# slow-movie-player.net
KiCad netlist of a schematic drawn in EasyEDA Pro
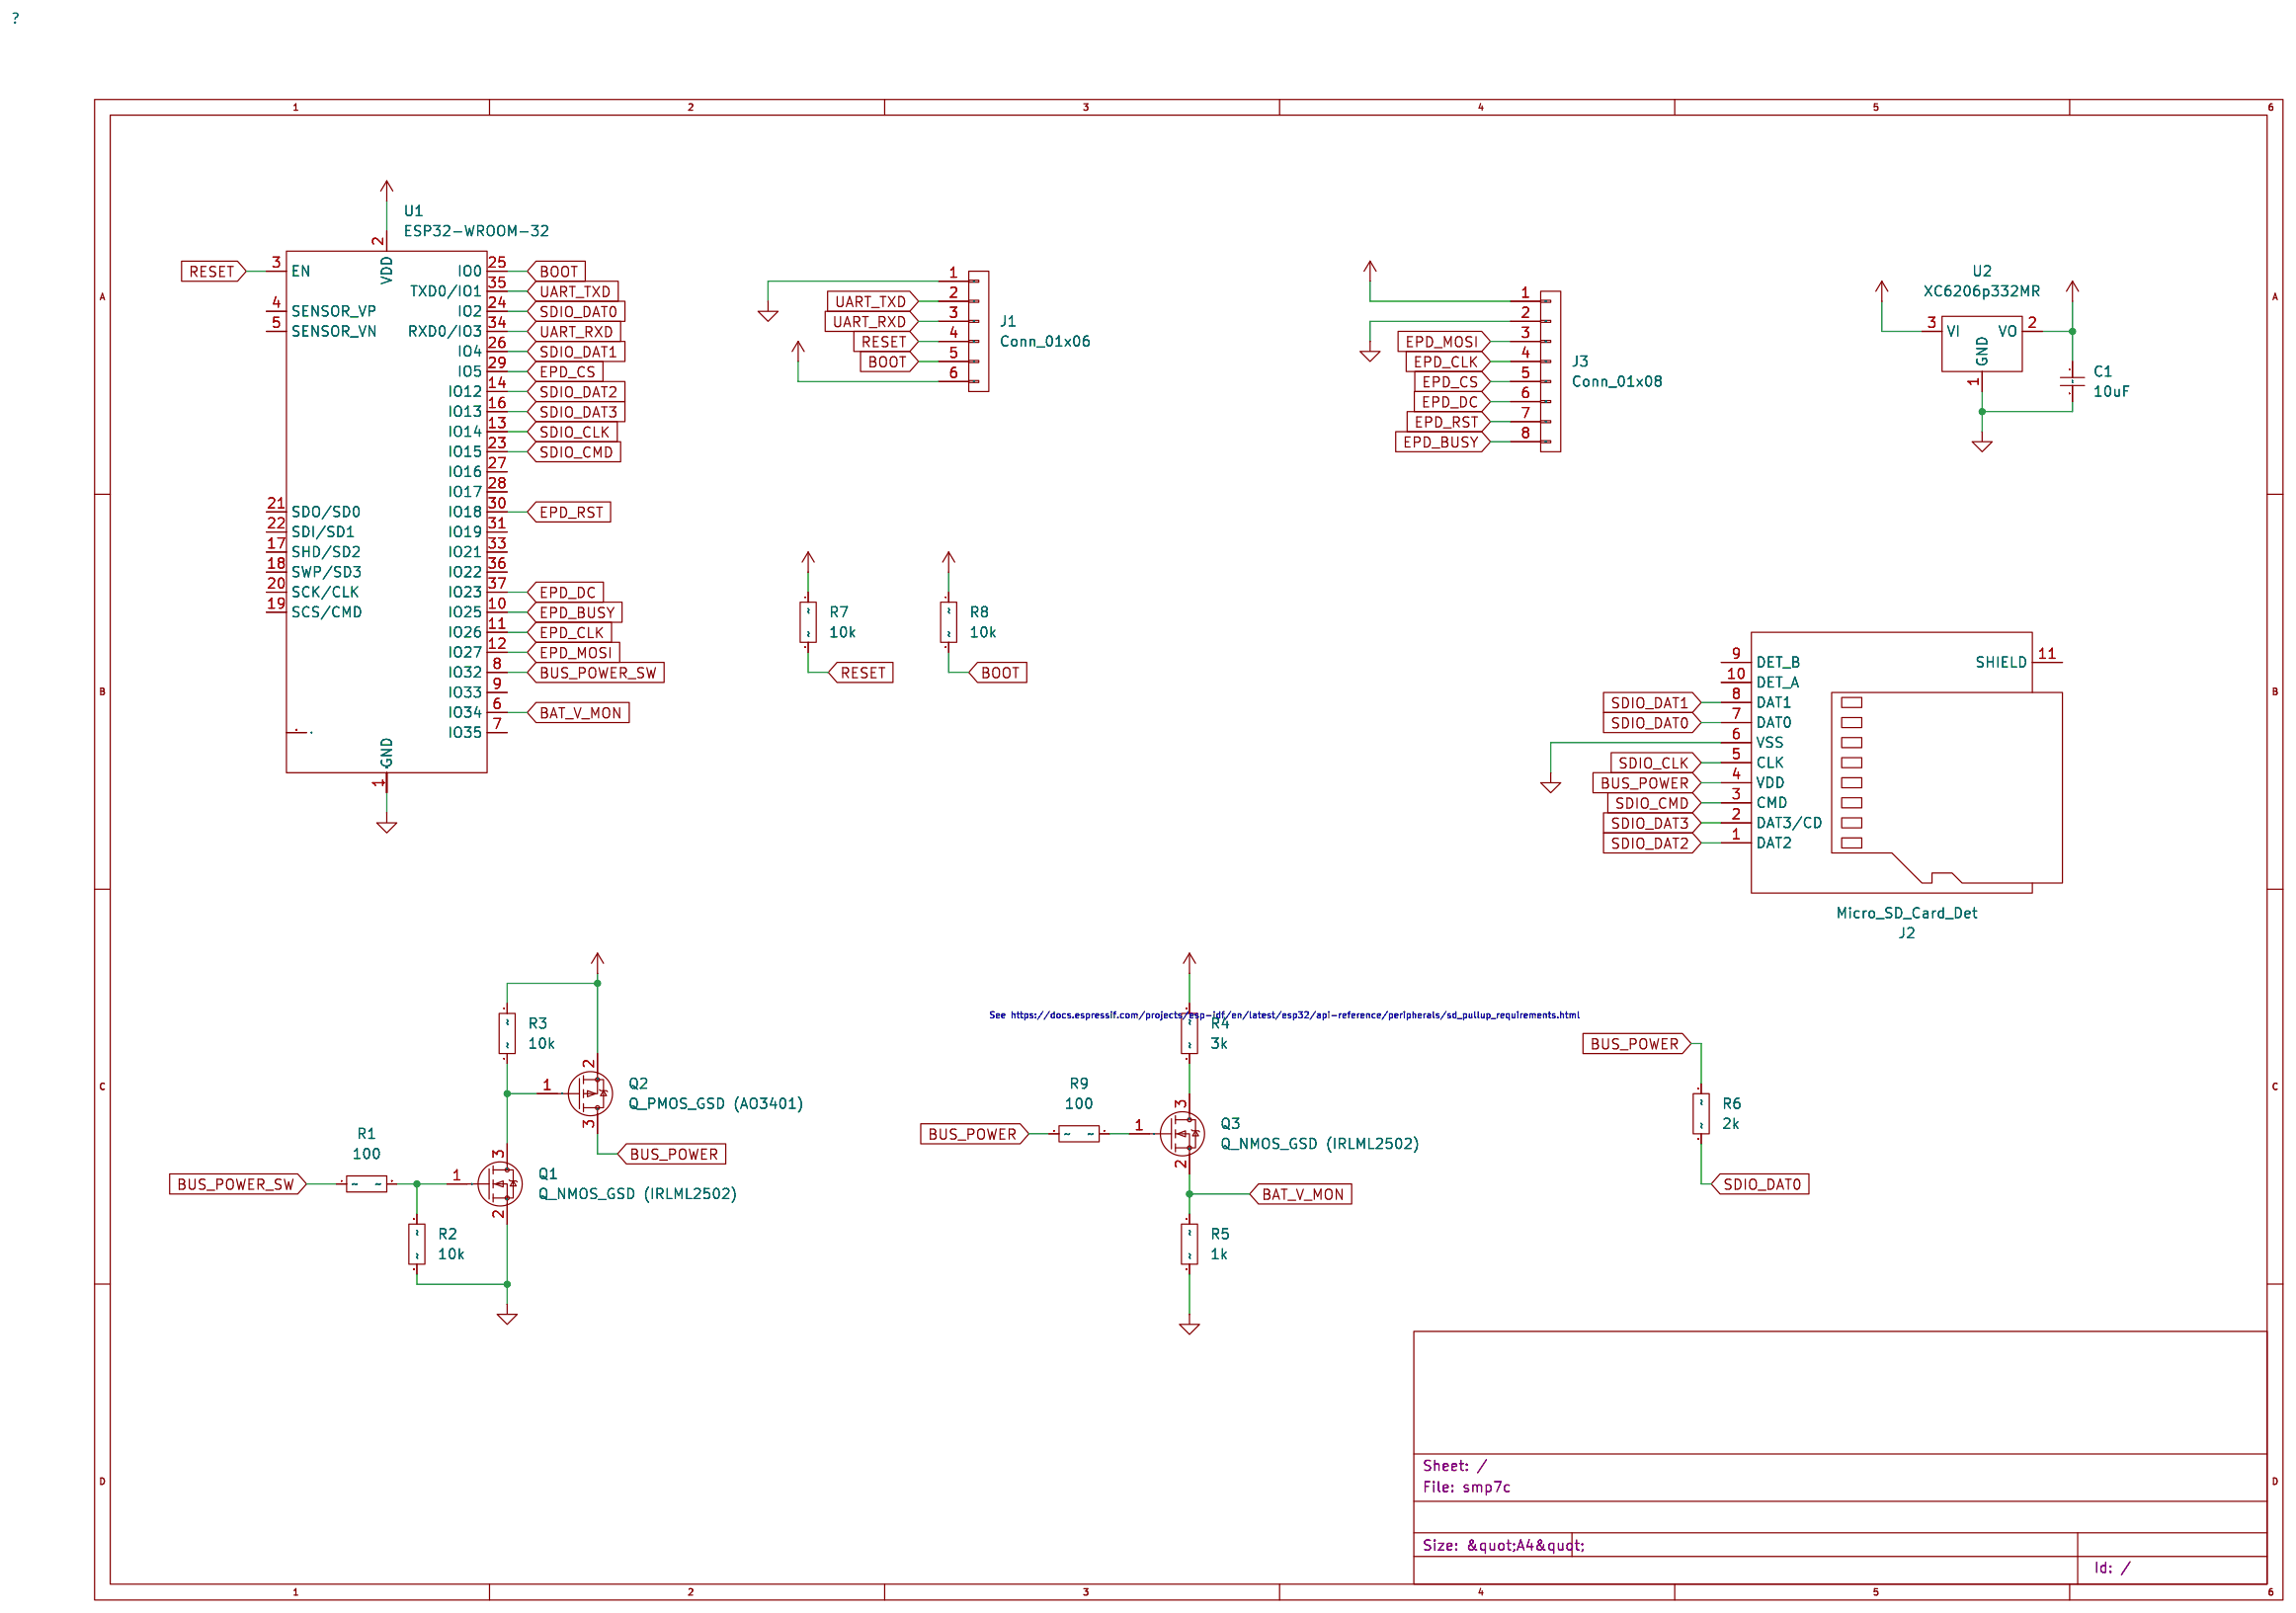
[diagram p0: schematic sheet]

(export (version "E")
  (design (tool "Eeschema 10.0.6"))
  (components
    (comp (ref "C1")
      (value "10uF")
      (footprint "easyedapro:Capacitor_SMD:C_1206_3216Metric")
      (libsource (lib "easyedapro") (part "Device_C_Small"))
    )
    (comp (ref "J1")
      (value "Conn_01x06")
      (footprint "easyedapro:Connector_PinSocket_2.54mm:PinSocket_1x06_P2.54mm_Vertical")
      (libsource (lib "easyedapro") (part "Connector_Generic_Conn_01x06"))
    )
    (comp (ref "J2")
      (value "Micro_SD_Card_Det")
      (footprint "easyedapro:Connector_Card:microSD_HC_Hirose_DM3BT-DSF-PEJS")
      (libsource (lib "easyedapro") (part "Connector_Micro_SD_Card_Det"))
    )
    (comp (ref "J3")
      (value "Conn_01x08")
      (footprint "easyedapro:Connector_PinSocket_2.54mm:PinSocket_1x08_P2.54mm_Vertical")
      (libsource (lib "easyedapro") (part "Connector_Generic_Conn_01x08"))
    )
    (comp (ref "Q1")
      (value "Q_NMOS_GSD (IRLML2502)")
      (footprint "easyedapro:Package_TO_SOT_SMD:SOT-23")
      (libsource (lib "easyedapro") (part "Device_Q_NMOS_GSD"))
    )
    (comp (ref "Q2")
      (value "Q_PMOS_GSD (AO3401)")
      (footprint "easyedapro:Package_TO_SOT_SMD:SOT-23")
      (libsource (lib "easyedapro") (part "Device_Q_PMOS_GSD"))
    )
    (comp (ref "Q3")
      (value "Q_NMOS_GSD (IRLML2502)")
      (footprint "easyedapro:Package_TO_SOT_SMD:SOT-23")
      (libsource (lib "easyedapro") (part "Device_Q_NMOS_GSD"))
    )
    (comp (ref "R1")
      (value "100")
      (footprint "easyedapro:Resistor_SMD:R_0603_1608Metric")
      (libsource (lib "easyedapro") (part "Device_R"))
    )
    (comp (ref "R2")
      (value "10k")
      (footprint "easyedapro:Resistor_SMD:R_0603_1608Metric")
      (libsource (lib "easyedapro") (part "Device_R"))
    )
    (comp (ref "R3")
      (value "10k")
      (footprint "easyedapro:Resistor_SMD:R_0603_1608Metric")
      (libsource (lib "easyedapro") (part "Device_R"))
    )
    (comp (ref "R4")
      (value "3k")
      (footprint "easyedapro:Resistor_SMD:R_0603_1608Metric")
      (libsource (lib "easyedapro") (part "Device_R"))
    )
    (comp (ref "R5")
      (value "1k")
      (footprint "easyedapro:Resistor_SMD:R_0603_1608Metric")
      (libsource (lib "easyedapro") (part "Device_R"))
    )
    (comp (ref "R6")
      (value "2k")
      (footprint "easyedapro:Resistor_SMD:R_0603_1608Metric")
      (libsource (lib "easyedapro") (part "Device_R"))
    )
    (comp (ref "R7")
      (value "10k")
      (footprint "easyedapro:Resistor_SMD:R_0603_1608Metric")
      (libsource (lib "easyedapro") (part "Device_R"))
    )
    (comp (ref "R8")
      (value "10k")
      (footprint "easyedapro:Resistor_SMD:R_0603_1608Metric")
      (libsource (lib "easyedapro") (part "Device_R"))
    )
    (comp (ref "R9")
      (value "100")
      (footprint "easyedapro:Resistor_SMD:R_0603_1608Metric")
      (libsource (lib "easyedapro") (part "Device_R"))
    )
    (comp (ref "U1")
      (value "ESP32-WROOM-32")
      (footprint "easyedapro:RF_Module:ESP32-WROOM-32")
      (libsource (lib "easyedapro") (part "RF_Module_ESP32-WROOM-32"))
    )
    (comp (ref "U2")
      (value "XC6206p332MR")
      (footprint "easyedapro:Package_TO_SOT_SMD:SOT-23")
      (libsource (lib "easyedapro") (part "Regulator_Linear_XC6206PxxxMR"))
    )
  )
  (nets
    (net (code "1") (name "BAT_V_MON") (class "Default")
      (node (ref "Q3") (pin "2") (pinfunction "S_2") (pintype "unspecified"))
      (node (ref "R5") (pin "1") (pinfunction "~_1") (pintype "unspecified"))
      (node (ref "U1") (pin "6") (pinfunction "IO34_6") (pintype "input"))
    )
    (net (code "2") (name "BOOT") (class "Default")
      (node (ref "J1") (pin "5") (pinfunction "Pin_5_5") (pintype "unspecified"))
      (node (ref "R8") (pin "2") (pinfunction "~_2") (pintype "unspecified"))
      (node (ref "U1") (pin "25") (pinfunction "IO0_25") (pintype "bidirectional"))
    )
    (net (code "3") (name "BUS_POWER") (class "Default")
      (node (ref "J2") (pin "4") (pinfunction "VDD_4") (pintype "unspecified"))
      (node (ref "Q2") (pin "3") (pinfunction "D_3") (pintype "unspecified"))
      (node (ref "R6") (pin "1") (pinfunction "~_1") (pintype "unspecified"))
      (node (ref "R9") (pin "1") (pinfunction "~_1") (pintype "unspecified"))
    )
    (net (code "4") (name "BUS_POWER_SW") (class "Default")
      (node (ref "R1") (pin "1") (pinfunction "~_1") (pintype "unspecified"))
      (node (ref "U1") (pin "8") (pinfunction "IO32_8") (pintype "bidirectional"))
    )
    (net (code "5") (name "EPD_BUSY") (class "Default")
      (node (ref "J3") (pin "8") (pinfunction "Pin_8_8") (pintype "unspecified"))
      (node (ref "U1") (pin "10") (pinfunction "IO25_10") (pintype "bidirectional"))
    )
    (net (code "6") (name "EPD_CLK") (class "Default")
      (node (ref "J3") (pin "4") (pinfunction "Pin_4_4") (pintype "unspecified"))
      (node (ref "U1") (pin "11") (pinfunction "IO26_11") (pintype "bidirectional"))
    )
    (net (code "7") (name "EPD_CS") (class "Default")
      (node (ref "J3") (pin "5") (pinfunction "Pin_5_5") (pintype "unspecified"))
      (node (ref "U1") (pin "29") (pinfunction "IO5_29") (pintype "bidirectional"))
    )
    (net (code "8") (name "EPD_DC") (class "Default")
      (node (ref "J3") (pin "6") (pinfunction "Pin_6_6") (pintype "unspecified"))
      (node (ref "U1") (pin "37") (pinfunction "IO23_37") (pintype "bidirectional"))
    )
    (net (code "9") (name "EPD_MOSI") (class "Default")
      (node (ref "J3") (pin "3") (pinfunction "Pin_3_3") (pintype "unspecified"))
      (node (ref "U1") (pin "12") (pinfunction "IO27_12") (pintype "bidirectional"))
    )
    (net (code "10") (name "EPD_RST") (class "Default")
      (node (ref "J3") (pin "7") (pinfunction "Pin_7_7") (pintype "unspecified"))
      (node (ref "U1") (pin "30") (pinfunction "IO18_30") (pintype "bidirectional"))
    )
    (net (code "11") (name "Net-(Q1-D)") (class "Default")
      (node (ref "Q1") (pin "3") (pinfunction "D_3") (pintype "unspecified"))
      (node (ref "Q2") (pin "1") (pinfunction "G_1") (pintype "input"))
      (node (ref "R3") (pin "2") (pinfunction "~_2") (pintype "unspecified"))
    )
    (net (code "12") (name "Net-(Q1-G)") (class "Default")
      (node (ref "Q1") (pin "1") (pinfunction "G_1") (pintype "input"))
      (node (ref "R1") (pin "2") (pinfunction "~_2") (pintype "unspecified"))
      (node (ref "R2") (pin "1") (pinfunction "~_1") (pintype "unspecified"))
    )
    (net (code "13") (name "Net-(Q3-D)") (class "Default")
      (node (ref "Q3") (pin "3") (pinfunction "D_3") (pintype "unspecified"))
      (node (ref "R4") (pin "2") (pinfunction "~_2") (pintype "unspecified"))
    )
    (net (code "14") (name "Net-(Q3-G)") (class "Default")
      (node (ref "Q3") (pin "1") (pinfunction "G_1") (pintype "input"))
      (node (ref "R9") (pin "2") (pinfunction "~_2") (pintype "unspecified"))
    )
    (net (code "15") (name "POWER_+3V3") (class "Default")
      (node (ref "C1") (pin "1") (pinfunction "~_1") (pintype "unspecified"))
      (node (ref "J1") (pin "6") (pinfunction "Pin_6_6") (pintype "unspecified"))
      (node (ref "J3") (pin "1") (pinfunction "Pin_1_1") (pintype "unspecified"))
      (node (ref "Q2") (pin "2") (pinfunction "S_2") (pintype "unspecified"))
      (node (ref "R3") (pin "1") (pinfunction "~_1") (pintype "unspecified"))
      (node (ref "R7") (pin "1") (pinfunction "~_1") (pintype "unspecified"))
      (node (ref "R8") (pin "1") (pinfunction "~_1") (pintype "unspecified"))
      (node (ref "U1") (pin "2") (pinfunction "VDD_2") (pintype "unspecified"))
      (node (ref "U2") (pin "2") (pinfunction "VO_2") (pintype "unspecified"))
    )
    (net (code "16") (name "POWER_+BATT") (class "Default")
      (node (ref "R4") (pin "1") (pinfunction "~_1") (pintype "unspecified"))
      (node (ref "U2") (pin "3") (pinfunction "VI_3") (pintype "unspecified"))
    )
    (net (code "17") (name "POWER_GND") (class "Default")
      (node (ref "C1") (pin "2") (pinfunction "~_2") (pintype "unspecified"))
      (node (ref "J1") (pin "1") (pinfunction "Pin_1_1") (pintype "unspecified"))
      (node (ref "J2") (pin "6") (pinfunction "VSS_6") (pintype "unspecified"))
      (node (ref "J3") (pin "2") (pinfunction "Pin_2_2") (pintype "unspecified"))
      (node (ref "Q1") (pin "2") (pinfunction "S_2") (pintype "unspecified"))
      (node (ref "R2") (pin "2") (pinfunction "~_2") (pintype "unspecified"))
      (node (ref "R5") (pin "2") (pinfunction "~_2") (pintype "unspecified"))
      (node (ref "U1") (pin "1") (pinfunction "GND_1") (pintype "unspecified"))
      (node (ref "U1") (pin "15") (pinfunction "GND_15") (pintype "unspecified"))
      (node (ref "U1") (pin "38") (pinfunction "GND_38") (pintype "unspecified"))
      (node (ref "U1") (pin "39") (pinfunction "GND_39") (pintype "unspecified"))
      (node (ref "U2") (pin "1") (pinfunction "GND_1") (pintype "unspecified"))
    )
    (net (code "18") (name "RESET") (class "Default")
      (node (ref "J1") (pin "4") (pinfunction "Pin_4_4") (pintype "unspecified"))
      (node (ref "R7") (pin "2") (pinfunction "~_2") (pintype "unspecified"))
      (node (ref "U1") (pin "3") (pinfunction "EN_3") (pintype "input"))
    )
    (net (code "19") (name "SDIO_CLK") (class "Default")
      (node (ref "J2") (pin "5") (pinfunction "CLK_5") (pintype "input"))
      (node (ref "U1") (pin "13") (pinfunction "IO14_13") (pintype "bidirectional"))
    )
    (net (code "20") (name "SDIO_CMD") (class "Default")
      (node (ref "J2") (pin "3") (pinfunction "CMD_3") (pintype "input"))
      (node (ref "U1") (pin "23") (pinfunction "IO15_23") (pintype "bidirectional"))
    )
    (net (code "21") (name "SDIO_DAT0") (class "Default")
      (node (ref "J2") (pin "7") (pinfunction "DAT0_7") (pintype "bidirectional"))
      (node (ref "R6") (pin "2") (pinfunction "~_2") (pintype "unspecified"))
      (node (ref "U1") (pin "24") (pinfunction "IO2_24") (pintype "bidirectional"))
    )
    (net (code "22") (name "SDIO_DAT1") (class "Default")
      (node (ref "J2") (pin "8") (pinfunction "DAT1_8") (pintype "bidirectional"))
      (node (ref "U1") (pin "26") (pinfunction "IO4_26") (pintype "bidirectional"))
    )
    (net (code "23") (name "SDIO_DAT2") (class "Default")
      (node (ref "J2") (pin "1") (pinfunction "DAT2_1") (pintype "bidirectional"))
      (node (ref "U1") (pin "14") (pinfunction "IO12_14") (pintype "bidirectional"))
    )
    (net (code "24") (name "SDIO_DAT3") (class "Default")
      (node (ref "J2") (pin "2") (pinfunction "DAT3/CD_2") (pintype "bidirectional"))
      (node (ref "U1") (pin "16") (pinfunction "IO13_16") (pintype "bidirectional"))
    )
    (net (code "25") (name "UART_RXD") (class "Default")
      (node (ref "J1") (pin "3") (pinfunction "Pin_3_3") (pintype "unspecified"))
      (node (ref "U1") (pin "34") (pinfunction "RXD0/IO3_34") (pintype "bidirectional"))
    )
    (net (code "26") (name "UART_TXD") (class "Default")
      (node (ref "J1") (pin "2") (pinfunction "Pin_2_2") (pintype "unspecified"))
      (node (ref "U1") (pin "35") (pinfunction "TXD0/IO1_35") (pintype "bidirectional"))
    )
    (net (code "27") (name "unconnected-(J2-DET_A-Pad10)") (class "Default")
      (node (ref "J2") (pin "10") (pinfunction "DET_A_10") (pintype "unspecified"))
    )
    (net (code "28") (name "unconnected-(J2-DET_B-Pad9)") (class "Default")
      (node (ref "J2") (pin "9") (pinfunction "DET_B_9") (pintype "unspecified"))
    )
    (net (code "29") (name "unconnected-(J2-SHIELD-Pad11)") (class "Default")
      (node (ref "J2") (pin "11") (pinfunction "SHIELD_11") (pintype "unspecified"))
    )
    (net (code "30") (name "unconnected-(U1-IO16-Pad27)") (class "Default")
      (node (ref "U1") (pin "27") (pinfunction "IO16_27") (pintype "bidirectional"))
    )
    (net (code "31") (name "unconnected-(U1-IO17-Pad28)") (class "Default")
      (node (ref "U1") (pin "28") (pinfunction "IO17_28") (pintype "bidirectional"))
    )
    (net (code "32") (name "unconnected-(U1-IO19-Pad31)") (class "Default")
      (node (ref "U1") (pin "31") (pinfunction "IO19_31") (pintype "bidirectional"))
    )
    (net (code "33") (name "unconnected-(U1-IO21-Pad33)") (class "Default")
      (node (ref "U1") (pin "33") (pinfunction "IO21_33") (pintype "bidirectional"))
    )
    (net (code "34") (name "unconnected-(U1-IO22-Pad36)") (class "Default")
      (node (ref "U1") (pin "36") (pinfunction "IO22_36") (pintype "bidirectional"))
    )
    (net (code "35") (name "unconnected-(U1-IO33-Pad9)") (class "Default")
      (node (ref "U1") (pin "9") (pinfunction "IO33_9") (pintype "bidirectional"))
    )
    (net (code "36") (name "unconnected-(U1-IO35-Pad7)") (class "Default")
      (node (ref "U1") (pin "7") (pinfunction "IO35_7") (pintype "input"))
    )
    (net (code "37") (name "unconnected-(U1-NC-Pad32)") (class "Default")
      (node (ref "U1") (pin "32") (pinfunction "NC_32") (pintype "unspecified"))
    )
    (net (code "38") (name "unconnected-(U1-SCK{slash}CLK-Pad20)") (class "Default")
      (node (ref "U1") (pin "20") (pinfunction "SCK/CLK_20") (pintype "bidirectional"))
    )
    (net (code "39") (name "unconnected-(U1-SCS{slash}CMD-Pad19)") (class "Default")
      (node (ref "U1") (pin "19") (pinfunction "SCS/CMD_19") (pintype "bidirectional"))
    )
    (net (code "40") (name "unconnected-(U1-SDI{slash}SD1-Pad22)") (class "Default")
      (node (ref "U1") (pin "22") (pinfunction "SDI/SD1_22") (pintype "bidirectional"))
    )
    (net (code "41") (name "unconnected-(U1-SDO{slash}SD0-Pad21)") (class "Default")
      (node (ref "U1") (pin "21") (pinfunction "SDO/SD0_21") (pintype "bidirectional"))
    )
    (net (code "42") (name "unconnected-(U1-SENSOR_VN-Pad5)") (class "Default")
      (node (ref "U1") (pin "5") (pinfunction "SENSOR_VN_5") (pintype "input"))
    )
    (net (code "43") (name "unconnected-(U1-SENSOR_VP-Pad4)") (class "Default")
      (node (ref "U1") (pin "4") (pinfunction "SENSOR_VP_4") (pintype "input"))
    )
    (net (code "44") (name "unconnected-(U1-SHD{slash}SD2-Pad17)") (class "Default")
      (node (ref "U1") (pin "17") (pinfunction "SHD/SD2_17") (pintype "bidirectional"))
    )
    (net (code "45") (name "unconnected-(U1-SWP{slash}SD3-Pad18)") (class "Default")
      (node (ref "U1") (pin "18") (pinfunction "SWP/SD3_18") (pintype "bidirectional"))
    )
  )
)
